# pd25.net
KiCad netlist of a schematic drawn in EAGLE
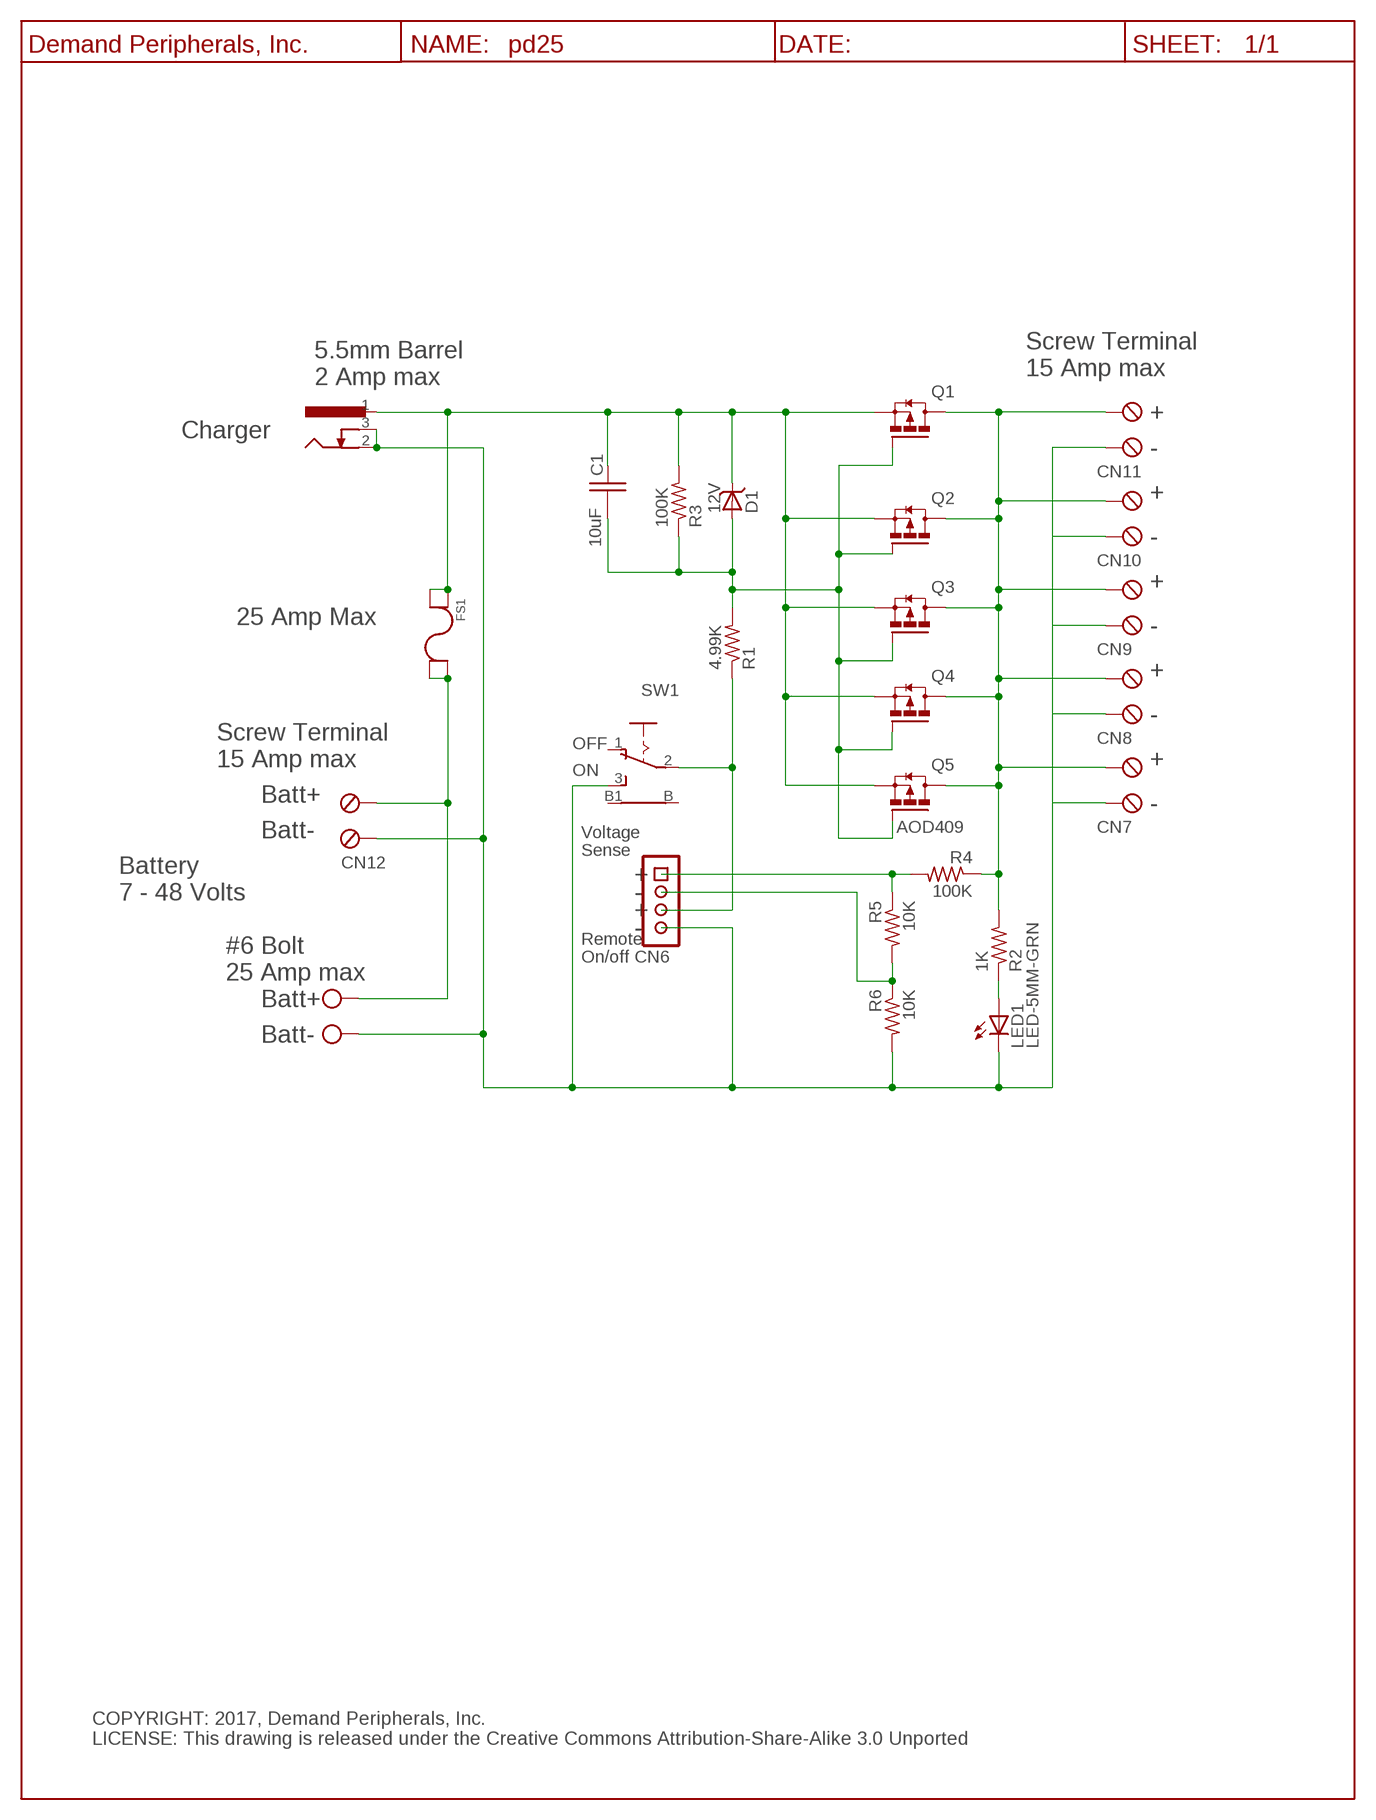
[diagram p0: schematic, sheet 1]

(export (version "E")
  (design (tool "Eeschema 10.0.6"))
  (components
    (comp (ref "BATT+")
      (value "Bolt_Connection")
      (footprint "eagle-import:BOLT_6")
      (libsource (lib "eagle-import") (part "BOLT_6"))
    )
    (comp (ref "BOLT1")
      (value "Bolt_Connection")
      (footprint "eagle-import:BOLT_6")
      (libsource (lib "eagle-import") (part "BOLT_6"))
    )
    (comp (ref "C1")
      (value "10uF")
      (footprint "eagle-import:C0805")
      (libsource (lib "eagle-import") (part "C10UF35V_C0805"))
    )
    (comp (ref "CN6")
      (value "HDR-4X1-LCK")
      (footprint "eagle-import:HDR-4X1")
      (libsource (lib "eagle-import") (part "HDR-4X1-LCK"))
    )
    (comp (ref "CN7")
      (value "TBLK-5.08-X2")
      (footprint "eagle-import:TBLK-5.08-X2")
      (libsource (lib "eagle-import") (part "TBLK-5.08-X2"))
    )
    (comp (ref "CN8")
      (value "TBLK-5.08-X2")
      (footprint "eagle-import:TBLK-5.08-X2")
      (libsource (lib "eagle-import") (part "TBLK-5.08-X2"))
    )
    (comp (ref "CN9")
      (value "TBLK-5.08-X2")
      (footprint "eagle-import:TBLK-5.08-X2")
      (libsource (lib "eagle-import") (part "TBLK-5.08-X2"))
    )
    (comp (ref "CN10")
      (value "TBLK-5.08-X2")
      (footprint "eagle-import:TBLK-5.08-X2")
      (libsource (lib "eagle-import") (part "TBLK-5.08-X2"))
    )
    (comp (ref "CN11")
      (value "TBLK-5.08-X2")
      (footprint "eagle-import:TBLK-5.08-X2")
      (libsource (lib "eagle-import") (part "TBLK-5.08-X2"))
    )
    (comp (ref "CN12")
      (value "TBLK-5.08-X2")
      (footprint "eagle-import:TBLK-5.08-X2")
      (libsource (lib "eagle-import") (part "TBLK-5.08-X2"))
    )
    (comp (ref "D1")
      (value "12V")
      (footprint "eagle-import:SOD123")
      (libsource (lib "eagle-import") (part "BZT52C12"))
    )
    (comp (ref "FS1")
      (value "FUSE-KS3557")
      (footprint "eagle-import:KS3557-10")
      (libsource (lib "eagle-import") (part "FUSE-KS3557"))
    )
    (comp (ref "J1")
      (value "Barrel-5.5mm")
      (footprint "eagle-import:DC-BARREL-JACK-55MM")
      (libsource (lib "eagle-import") (part "DC-BARREL-JACK--55MM"))
    )
    (comp (ref "LED1")
      (value "LED-5MM-GRN")
      (footprint "eagle-import:LED5MM")
      (libsource (lib "eagle-import") (part "LED-5MM-GRN"))
    )
    (comp (ref "Q1")
      (value "FET_DPAK_P")
      (footprint "eagle-import:DPACK_TO-252")
      (libsource (lib "eagle-import") (part "AOD409"))
    )
    (comp (ref "Q2")
      (value "FET_DPAK_P")
      (footprint "eagle-import:DPACK_TO-252")
      (libsource (lib "eagle-import") (part "AOD409"))
    )
    (comp (ref "Q3")
      (value "FET_DPAK_P")
      (footprint "eagle-import:DPACK_TO-252")
      (libsource (lib "eagle-import") (part "AOD409"))
    )
    (comp (ref "Q4")
      (value "FET_DPAK_P")
      (footprint "eagle-import:DPACK_TO-252")
      (libsource (lib "eagle-import") (part "AOD409"))
    )
    (comp (ref "Q5")
      (value "AOD409")
      (footprint "eagle-import:DPACK_TO-252")
      (libsource (lib "eagle-import") (part "AOD409"))
    )
    (comp (ref "R1")
      (value "4.99K")
      (footprint "eagle-import:R0603")
      (libsource (lib "eagle-import") (part "R4.99K_R0603"))
    )
    (comp (ref "R2")
      (value "1K")
      (footprint "eagle-import:R0603")
      (libsource (lib "eagle-import") (part "R1K_R0603"))
    )
    (comp (ref "R3")
      (value "100K")
      (footprint "eagle-import:R0603")
      (libsource (lib "eagle-import") (part "R100K_R0603"))
    )
    (comp (ref "R4")
      (value "100K")
      (footprint "eagle-import:R0603")
      (libsource (lib "eagle-import") (part "R100K_R0603"))
    )
    (comp (ref "R5")
      (value "10K")
      (footprint "eagle-import:R0603")
      (libsource (lib "eagle-import") (part "R10K_R0603"))
    )
    (comp (ref "R6")
      (value "10K")
      (footprint "eagle-import:R0603")
      (libsource (lib "eagle-import") (part "R10K_R0603"))
    )
    (comp (ref "SW1")
      (value "TOGGLE_SPDT_PC")
      (footprint "eagle-import:TOGGLE_SPDT_PC")
      (libsource (lib "eagle-import") (part "TOGGLE_SPDT_PC"))
    )
    (comp (ref "U$1")
      (value "DP_FRAME_P")
      (footprint "eagle-import:P_FRAME")
      (libsource (lib "eagle-import") (part "DP_FRAME_P"))
    )
  )
  (nets
    (net (code "1") (name "Net-(CN6-Pad1)") (class "Default")
      (node (ref "CN6") (pin "1") (pinfunction "1_1") (pintype "passive"))
      (node (ref "R4") (pin "2") (pinfunction "2_2") (pintype "passive"))
      (node (ref "R5") (pin "1") (pinfunction "1_1") (pintype "passive"))
    )
    (net (code "2") (name "Net-(CN6-Pad2)") (class "Default")
      (node (ref "CN6") (pin "2") (pinfunction "2_2") (pintype "passive"))
      (node (ref "R5") (pin "2") (pinfunction "2_2") (pintype "passive"))
      (node (ref "R6") (pin "1") (pinfunction "1_1") (pintype "passive"))
    )
    (net (code "3") (name "Net-(CN10-KL)") (class "Default")
      (node (ref "BOLT1") (pin "P") (pinfunction "P_P") (pintype "passive"))
      (node (ref "CN10") (pin "1") (pinfunction "KL_1") (pintype "passive"))
      (node (ref "CN11") (pin "1") (pinfunction "KL_1") (pintype "passive"))
      (node (ref "CN12") (pin "1") (pinfunction "KL_1") (pintype "passive"))
      (node (ref "CN6") (pin "4") (pinfunction "4_4") (pintype "passive"))
      (node (ref "CN7") (pin "1") (pinfunction "KL_1") (pintype "passive"))
      (node (ref "CN8") (pin "1") (pinfunction "KL_1") (pintype "passive"))
      (node (ref "CN9") (pin "1") (pinfunction "KL_1") (pintype "passive"))
      (node (ref "J1") (pin "2") (pinfunction "2_2") (pintype "passive"))
      (node (ref "J1") (pin "3") (pinfunction "3_3") (pintype "passive"))
      (node (ref "LED1") (pin "C") (pinfunction "C_C") (pintype "passive"))
      (node (ref "R6") (pin "2") (pinfunction "2_2") (pintype "passive"))
      (node (ref "SW1") (pin "3") (pinfunction "S_3") (pintype "passive"))
    )
    (net (code "4") (name "Net-(CN10-KL1)") (class "Default")
      (node (ref "CN10") (pin "2") (pinfunction "KL1_2") (pintype "passive"))
      (node (ref "CN11") (pin "2") (pinfunction "KL1_2") (pintype "passive"))
      (node (ref "CN7") (pin "2") (pinfunction "KL1_2") (pintype "passive"))
      (node (ref "CN8") (pin "2") (pinfunction "KL1_2") (pintype "passive"))
      (node (ref "CN9") (pin "2") (pinfunction "KL1_2") (pintype "passive"))
      (node (ref "Q1") (pin "4") (pinfunction "D_4") (pintype "passive"))
      (node (ref "Q2") (pin "4") (pinfunction "D_4") (pintype "passive"))
      (node (ref "Q3") (pin "4") (pinfunction "D_4") (pintype "passive"))
      (node (ref "Q4") (pin "4") (pinfunction "D_4") (pintype "passive"))
      (node (ref "Q5") (pin "4") (pinfunction "D_4") (pintype "passive"))
      (node (ref "R2") (pin "2") (pinfunction "2_2") (pintype "passive"))
      (node (ref "R4") (pin "1") (pinfunction "1_1") (pintype "passive"))
    )
    (net (code "5") (name "Net-(CN12-KL1)") (class "Default")
      (node (ref "BATT+") (pin "P") (pinfunction "P_P") (pintype "passive"))
      (node (ref "CN12") (pin "2") (pinfunction "KL1_2") (pintype "passive"))
      (node (ref "FS1") (pin "RS@3") (pinfunction "RS_RS@3") (pintype "power_in"))
      (node (ref "FS1") (pin "RS@4") (pinfunction "RS_RS@4") (pintype "power_in"))
    )
    (net (code "6") (name "Net-(LED1-PadA)") (class "Default")
      (node (ref "LED1") (pin "A") (pinfunction "A_A") (pintype "passive"))
      (node (ref "R2") (pin "1") (pinfunction "1_1") (pintype "passive"))
    )
    (net (code "7") (name "Net-(Q1-G)") (class "Default")
      (node (ref "C1") (pin "2") (pinfunction "2_2") (pintype "passive"))
      (node (ref "D1") (pin "A") (pinfunction "A_A") (pintype "passive"))
      (node (ref "Q1") (pin "1") (pinfunction "G_1") (pintype "passive"))
      (node (ref "Q2") (pin "1") (pinfunction "G_1") (pintype "passive"))
      (node (ref "Q3") (pin "1") (pinfunction "G_1") (pintype "passive"))
      (node (ref "Q4") (pin "1") (pinfunction "G_1") (pintype "passive"))
      (node (ref "Q5") (pin "1") (pinfunction "G_1") (pintype "passive"))
      (node (ref "R1") (pin "2") (pinfunction "2_2") (pintype "passive"))
      (node (ref "R3") (pin "1") (pinfunction "1_1") (pintype "passive"))
    )
    (net (code "8") (name "Net-(Q1-S)") (class "Default")
      (node (ref "C1") (pin "1") (pinfunction "1_1") (pintype "passive"))
      (node (ref "D1") (pin "C") (pinfunction "C_C") (pintype "passive"))
      (node (ref "FS1") (pin "LS@1") (pinfunction "LS_LS@1") (pintype "power_in"))
      (node (ref "FS1") (pin "LS@2") (pinfunction "LS_LS@2") (pintype "power_in"))
      (node (ref "J1") (pin "1") (pinfunction "1_1") (pintype "passive"))
      (node (ref "Q1") (pin "3") (pinfunction "S_3") (pintype "passive"))
      (node (ref "Q2") (pin "3") (pinfunction "S_3") (pintype "passive"))
      (node (ref "Q3") (pin "3") (pinfunction "S_3") (pintype "passive"))
      (node (ref "Q4") (pin "3") (pinfunction "S_3") (pintype "passive"))
      (node (ref "Q5") (pin "3") (pinfunction "S_3") (pintype "passive"))
      (node (ref "R3") (pin "2") (pinfunction "2_2") (pintype "passive"))
    )
    (net (code "9") (name "Net-(SW1-P)") (class "Default")
      (node (ref "CN6") (pin "3") (pinfunction "3_3") (pintype "passive"))
      (node (ref "R1") (pin "1") (pinfunction "1_1") (pintype "passive"))
      (node (ref "SW1") (pin "2") (pinfunction "P_2") (pintype "passive"))
    )
    (net (code "10") (name "unconnected-(SW1-O-Pad1)") (class "Default")
      (node (ref "SW1") (pin "1") (pinfunction "O_1") (pintype "passive"))
    )
    (net (code "11") (name "unconnected-(SW1-PadB)") (class "Default")
      (node (ref "SW1") (pin "B") (pinfunction "B_B") (pintype "passive"))
    )
    (net (code "12") (name "unconnected-(SW1-PadB1)") (class "Default")
      (node (ref "SW1") (pin "B1") (pinfunction "B1_B1") (pintype "passive"))
    )
  )
)
